# Vanta-Black_v4.net
KiCad netlist of a schematic drawn in EAGLE
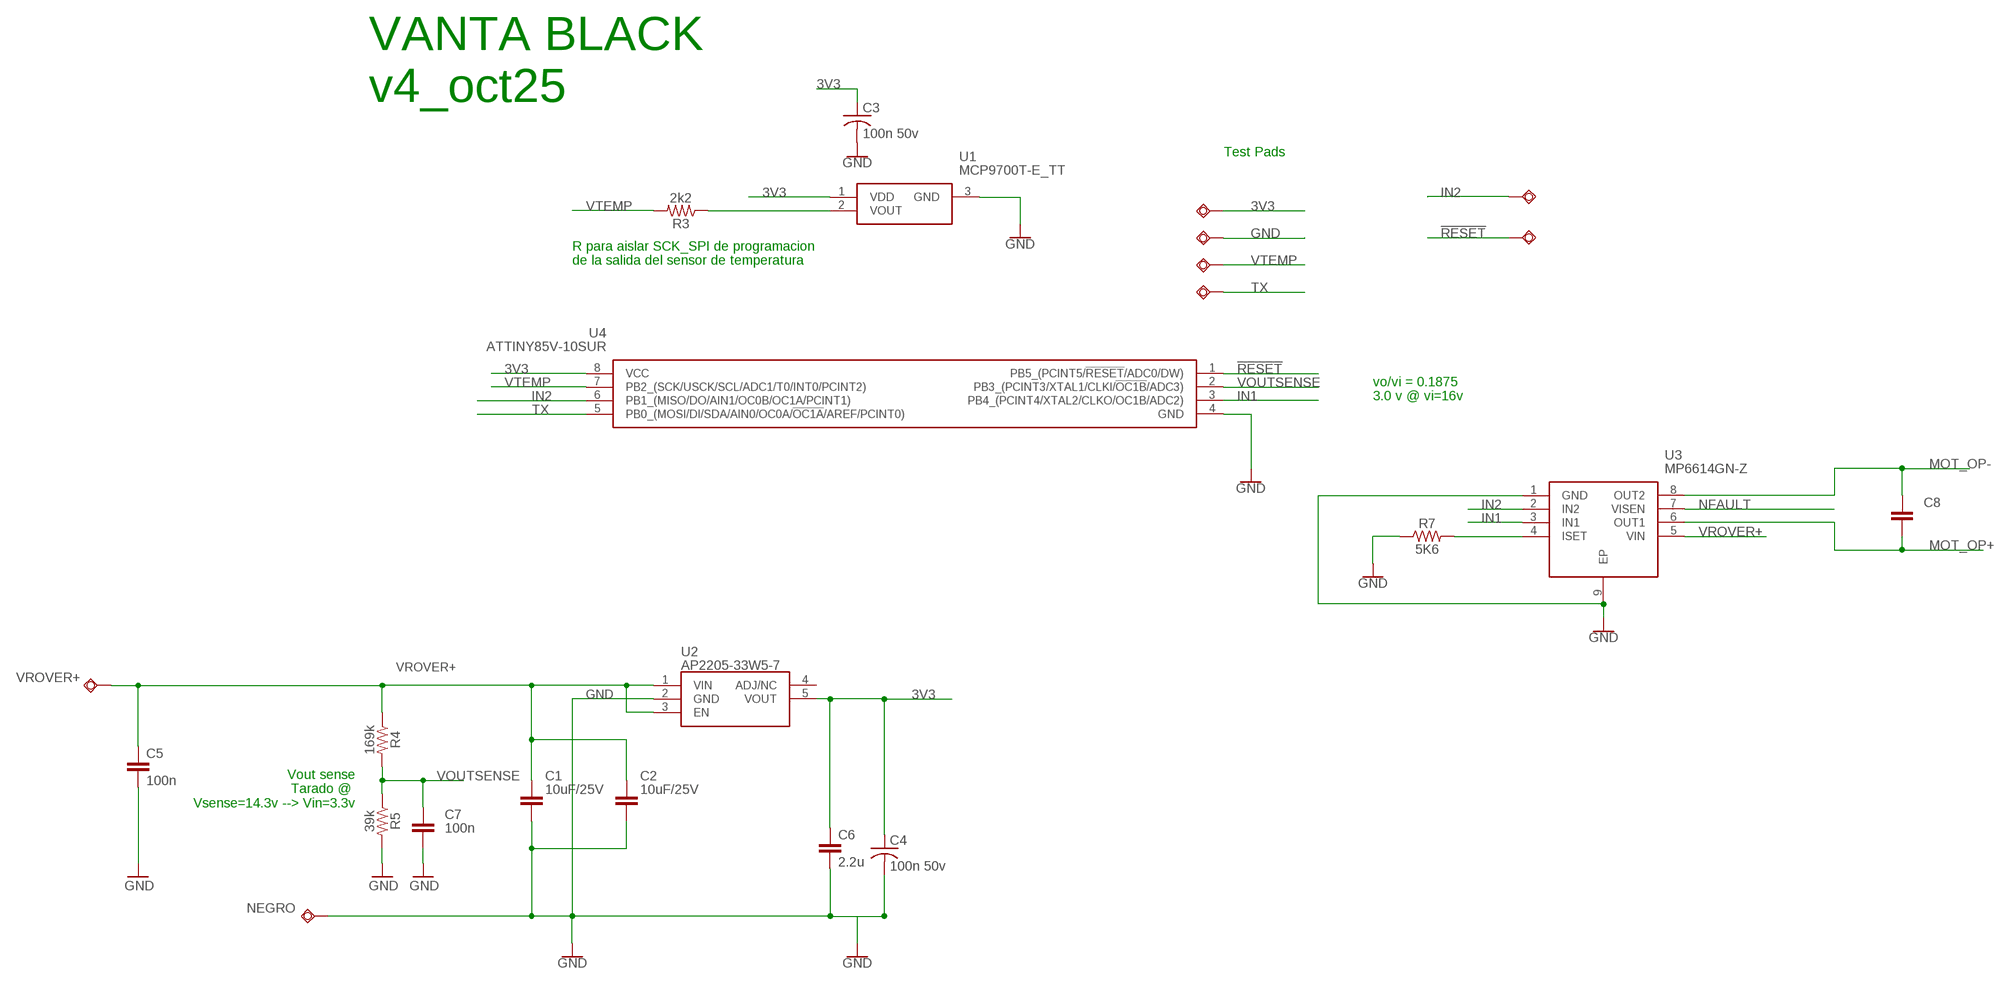
[diagram p0: schematic, sheet 1]

(export (version "E")
  (design (tool "Eeschema 10.0.6"))
  (components
    (comp (ref "!RST")
      (value "TESTPAD_TPSQB1,27")
      (footprint "eagle-import:TESTPAD_B1,27")
      (libsource (lib "eagle-import") (part "TESTPAD_TPSQB1,27"))
    )
    (comp (ref "3V3")
      (value "TESTPAD_TPSQB1,27")
      (footprint "eagle-import:TESTPAD_B1,27")
      (libsource (lib "eagle-import") (part "TESTPAD_TPSQB1,27"))
    )
    (comp (ref "C1")
      (value "10uF/25V")
      (footprint "eagle-import:CAPC2012X110")
      (libsource (lib "eagle-import") (part "CCHIP-0805(2012-METRIC)_"))
    )
    (comp (ref "C2")
      (value "10uF/25V")
      (footprint "eagle-import:CAPC2012X110")
      (libsource (lib "eagle-import") (part "CCHIP-0805(2012-METRIC)_"))
    )
    (comp (ref "C3")
      (value "100n 50v")
      (footprint "eagle-import:C0805")
      (libsource (lib "eagle-import") (part "C-USC0805"))
    )
    (comp (ref "C4")
      (value "100n 50v")
      (footprint "eagle-import:C0805")
      (libsource (lib "eagle-import") (part "C-USC0805"))
    )
    (comp (ref "C5")
      (value "100n")
      (footprint "eagle-import:0603-CAP")
      (libsource (lib "eagle-import") (part "4.7UF-6.3V-10%(0603)0603"))
    )
    (comp (ref "C6")
      (value "2.2u")
      (footprint "eagle-import:0603-CAP")
      (libsource (lib "eagle-import") (part "4.7UF-6.3V-10%(0603)0603"))
    )
    (comp (ref "C7")
      (value "100n")
      (footprint "eagle-import:0603")
      (libsource (lib "eagle-import") (part "0.1UF-0603-25V-(+80/-20%)"))
    )
    (comp (ref "C8")
      (value "100n")
      (footprint "eagle-import:0805")
      (libsource (lib "eagle-import") (part "CAP0805"))
    )
    (comp (ref "GND")
      (value "TESTPAD_TPSQB1,27")
      (footprint "eagle-import:TESTPAD_B1,27")
      (libsource (lib "eagle-import") (part "TESTPAD_TPSQB1,27"))
    )
    (comp (ref "IN2")
      (value "TESTPAD_TPSQB1,27")
      (footprint "eagle-import:TESTPAD_B1,27")
      (libsource (lib "eagle-import") (part "TESTPAD_TPSQB1,27"))
    )
    (comp (ref "NEGRO")
      (value "TESTPAD_TPSQTP10SQ")
      (footprint "eagle-import:TESTPAD_TP10SQ")
      (libsource (lib "eagle-import") (part "BeagleBone_Blue_R3_5828899_TESTPAD_TPSQTP10SQ"))
    )
    (comp (ref "R3")
      (value "2k2")
      (footprint "eagle-import:0603")
      (libsource (lib "eagle-import") (part "RESISTOR0603"))
    )
    (comp (ref "R4")
      (value "169k")
      (footprint "eagle-import:0603")
      (libsource (lib "eagle-import") (part "RESISTOR0603"))
    )
    (comp (ref "R5")
      (value "39k")
      (footprint "eagle-import:0603")
      (libsource (lib "eagle-import") (part "RESISTOR0603"))
    )
    (comp (ref "R7")
      (value "5K6")
      (footprint "eagle-import:0603")
      (libsource (lib "eagle-import") (part "RESISTOR0603"))
    )
    (comp (ref "TX")
      (value "TESTPAD_TPSQB1,27")
      (footprint "eagle-import:TESTPAD_B1,27")
      (libsource (lib "eagle-import") (part "TESTPAD_TPSQB1,27"))
    )
    (comp (ref "U1")
      (value "MCP9700T-E_TT")
      (footprint "eagle-import:SOT95P237X112-3N")
      (fields
        (field (name "ARROW_PART_NUMBER") "MCP9700T-E/TT")
        (field (name "MOUSER_PART_NUMBER") "579-MCP9700T-E/TT")
      )
      (libsource (lib "eagle-import") (part "MCP9700T-E_TT"))
    )
    (comp (ref "U2")
      (value "AP2205-33W5-7")
      (footprint "eagle-import:SOT95P282X145-5N")
      (fields
        (field (name "MANUFACTURER_PART_NUMBER") "AP2205-W5-7")
        (field (name "MOUSER_PART_NUMBER") "621-AP2205-W5-7")
      )
      (libsource (lib "eagle-import") (part "AP2205-W5-7"))
    )
    (comp (ref "U3")
      (value "MP6614GN-Z")
      (footprint "eagle-import:SOIC127P600X170-9N")
      (fields (field (name "MOUSER_PART_NUMBER") "946-MP6614GN-Z"))
      (libsource (lib "eagle-import") (part "MP6614GN-Z"))
    )
    (comp (ref "U4")
      (value "ATTINY85V-10SUR")
      (footprint "eagle-import:SOIC127P798X216-8N")
      (fields (field (name "FARNELL2_PART_NUMBER") "2851618RL"))
      (libsource (lib "eagle-import") (part "ATTINY85V-10SUR"))
    )
    (comp (ref "VISEN")
      (value "TESTPAD_TPSQB1,27")
      (footprint "eagle-import:TESTPAD_B1,27")
      (libsource (lib "eagle-import") (part "TESTPAD_TPSQB1,27"))
    )
    (comp (ref "VROVER+")
      (value "TESTPAD_TPSQTP10SQ")
      (footprint "eagle-import:TESTPAD_TP10SQ")
      (libsource (lib "eagle-import") (part "BeagleBone_Blue_R3_5828899_TESTPAD_TPSQTP10SQ"))
    )
  )
  (nets
    (net (code "1") (name "/3V3") (class "Default")
      (node (ref "3V3") (pin "TP") (pinfunction "TP_TP") (pintype "input"))
      (node (ref "C3") (pin "1") (pinfunction "1_1") (pintype "passive"))
      (node (ref "C4") (pin "1") (pinfunction "1_1") (pintype "passive"))
      (node (ref "C6") (pin "1") (pinfunction "1_1") (pintype "passive"))
      (node (ref "U1") (pin "1") (pinfunction "VDD_1") (pintype "bidirectional"))
      (node (ref "U2") (pin "5") (pinfunction "VOUT_5") (pintype "bidirectional"))
      (node (ref "U4") (pin "8") (pinfunction "VCC_8") (pintype "bidirectional"))
    )
    (net (code "2") (name "/IN1") (class "Default")
      (node (ref "U3") (pin "3") (pinfunction "IN1_3") (pintype "bidirectional"))
      (node (ref "U4") (pin "3") (pinfunction "PB4_(PCINT4/XTAL2/CLKO/OC1B/ADC2)_3") (pintype "bidirectional"))
    )
    (net (code "3") (name "/IN2") (class "Default")
      (node (ref "IN2") (pin "TP") (pinfunction "TP_TP") (pintype "input"))
      (node (ref "U3") (pin "2") (pinfunction "IN2_2") (pintype "bidirectional"))
      (node (ref "U4") (pin "6") (pinfunction "PB1_(MISO/DO/AIN1/OC0B/OC1A/PCINT1)_6") (pintype "bidirectional"))
    )
    (net (code "4") (name "/MOT_OP+") (class "Default")
      (node (ref "C8") (pin "2") (pinfunction "2_2") (pintype "passive"))
      (node (ref "U3") (pin "6") (pinfunction "OUT1_6") (pintype "bidirectional"))
    )
    (net (code "5") (name "/MOT_OP-") (class "Default")
      (node (ref "C8") (pin "1") (pinfunction "1_1") (pintype "passive"))
      (node (ref "U3") (pin "8") (pinfunction "OUT2_8") (pintype "bidirectional"))
    )
    (net (code "6") (name "/NFAULT") (class "Default")
      (node (ref "U3") (pin "7") (pinfunction "VISEN_7") (pintype "bidirectional"))
    )
    (net (code "7") (name "/TX") (class "Default")
      (node (ref "TX") (pin "TP") (pinfunction "TP_TP") (pintype "input"))
      (node (ref "U4") (pin "5") (pinfunction "PB0_(MOSI/DI/SDA/AIN0/OC0A/~{OC1A}/AREF/PCINT0)_5") (pintype "bidirectional"))
    )
    (net (code "8") (name "/VOUTSENSE") (class "Default")
      (node (ref "C7") (pin "1") (pinfunction "1_1") (pintype "passive"))
      (node (ref "R4") (pin "2") (pinfunction "2_2") (pintype "passive"))
      (node (ref "R5") (pin "1") (pinfunction "1_1") (pintype "passive"))
      (node (ref "U4") (pin "2") (pinfunction "PB3_(PCINT3/XTAL1/CLKI/~{OC1B}/ADC3)_2") (pintype "bidirectional"))
    )
    (net (code "9") (name "/VROVER+") (class "Default")
      (node (ref "C1") (pin "1") (pinfunction "1_1") (pintype "passive"))
      (node (ref "C2") (pin "1") (pinfunction "1_1") (pintype "passive"))
      (node (ref "C5") (pin "1") (pinfunction "1_1") (pintype "passive"))
      (node (ref "R4") (pin "1") (pinfunction "1_1") (pintype "passive"))
      (node (ref "U2") (pin "1") (pinfunction "VIN_1") (pintype "bidirectional"))
      (node (ref "U2") (pin "3") (pinfunction "EN_3") (pintype "bidirectional"))
      (node (ref "U3") (pin "5") (pinfunction "VIN_5") (pintype "bidirectional"))
      (node (ref "VROVER+") (pin "TP") (pinfunction "TP_TP") (pintype "input"))
    )
    (net (code "10") (name "/VTEMP") (class "Default")
      (node (ref "R3") (pin "2") (pinfunction "2_2") (pintype "passive"))
      (node (ref "U4") (pin "7") (pinfunction "PB2_(SCK/USCK/SCL/ADC1/T0/INT0/PCINT2)_7") (pintype "bidirectional"))
      (node (ref "VISEN") (pin "TP") (pinfunction "TP_TP") (pintype "input"))
    )
    (net (code "11") (name "/~{RESET}") (class "Default")
      (node (ref "!RST") (pin "TP") (pinfunction "TP_TP") (pintype "input"))
      (node (ref "U4") (pin "1") (pinfunction "PB5_(PCINT5/~{RESET}/ADC0/DW)_1") (pintype "bidirectional"))
    )
    (net (code "12") (name "GND") (class "Default")
      (node (ref "C1") (pin "2") (pinfunction "2_2") (pintype "passive"))
      (node (ref "C2") (pin "2") (pinfunction "2_2") (pintype "passive"))
      (node (ref "C3") (pin "2") (pinfunction "2_2") (pintype "passive"))
      (node (ref "C4") (pin "2") (pinfunction "2_2") (pintype "passive"))
      (node (ref "C5") (pin "2") (pinfunction "2_2") (pintype "passive"))
      (node (ref "C6") (pin "2") (pinfunction "2_2") (pintype "passive"))
      (node (ref "C7") (pin "2") (pinfunction "2_2") (pintype "passive"))
      (node (ref "GND") (pin "TP") (pinfunction "TP_TP") (pintype "input"))
      (node (ref "NEGRO") (pin "TP") (pinfunction "TP_TP") (pintype "input"))
      (node (ref "R5") (pin "2") (pinfunction "2_2") (pintype "passive"))
      (node (ref "R7") (pin "1") (pinfunction "1_1") (pintype "passive"))
      (node (ref "U1") (pin "3") (pinfunction "GND_3") (pintype "bidirectional"))
      (node (ref "U2") (pin "2") (pinfunction "GND_2") (pintype "bidirectional"))
      (node (ref "U3") (pin "1") (pinfunction "GND_1") (pintype "bidirectional"))
      (node (ref "U3") (pin "9") (pinfunction "EP_9") (pintype "bidirectional"))
      (node (ref "U4") (pin "4") (pinfunction "GND_4") (pintype "bidirectional"))
    )
    (net (code "13") (name "Net-(U1-VOUT)") (class "Default")
      (node (ref "R3") (pin "1") (pinfunction "1_1") (pintype "passive"))
      (node (ref "U1") (pin "2") (pinfunction "VOUT_2") (pintype "bidirectional"))
    )
    (net (code "14") (name "Net-(U3-ISET)") (class "Default")
      (node (ref "R7") (pin "2") (pinfunction "2_2") (pintype "passive"))
      (node (ref "U3") (pin "4") (pinfunction "ISET_4") (pintype "bidirectional"))
    )
    (net (code "15") (name "unconnected-(U2-ADJ{slash}NC-Pad4)") (class "Default")
      (node (ref "U2") (pin "4") (pinfunction "ADJ/NC_4") (pintype "bidirectional"))
    )
  )
)
